# irkit_v02.net
KiCad netlist of a schematic drawn in EAGLE
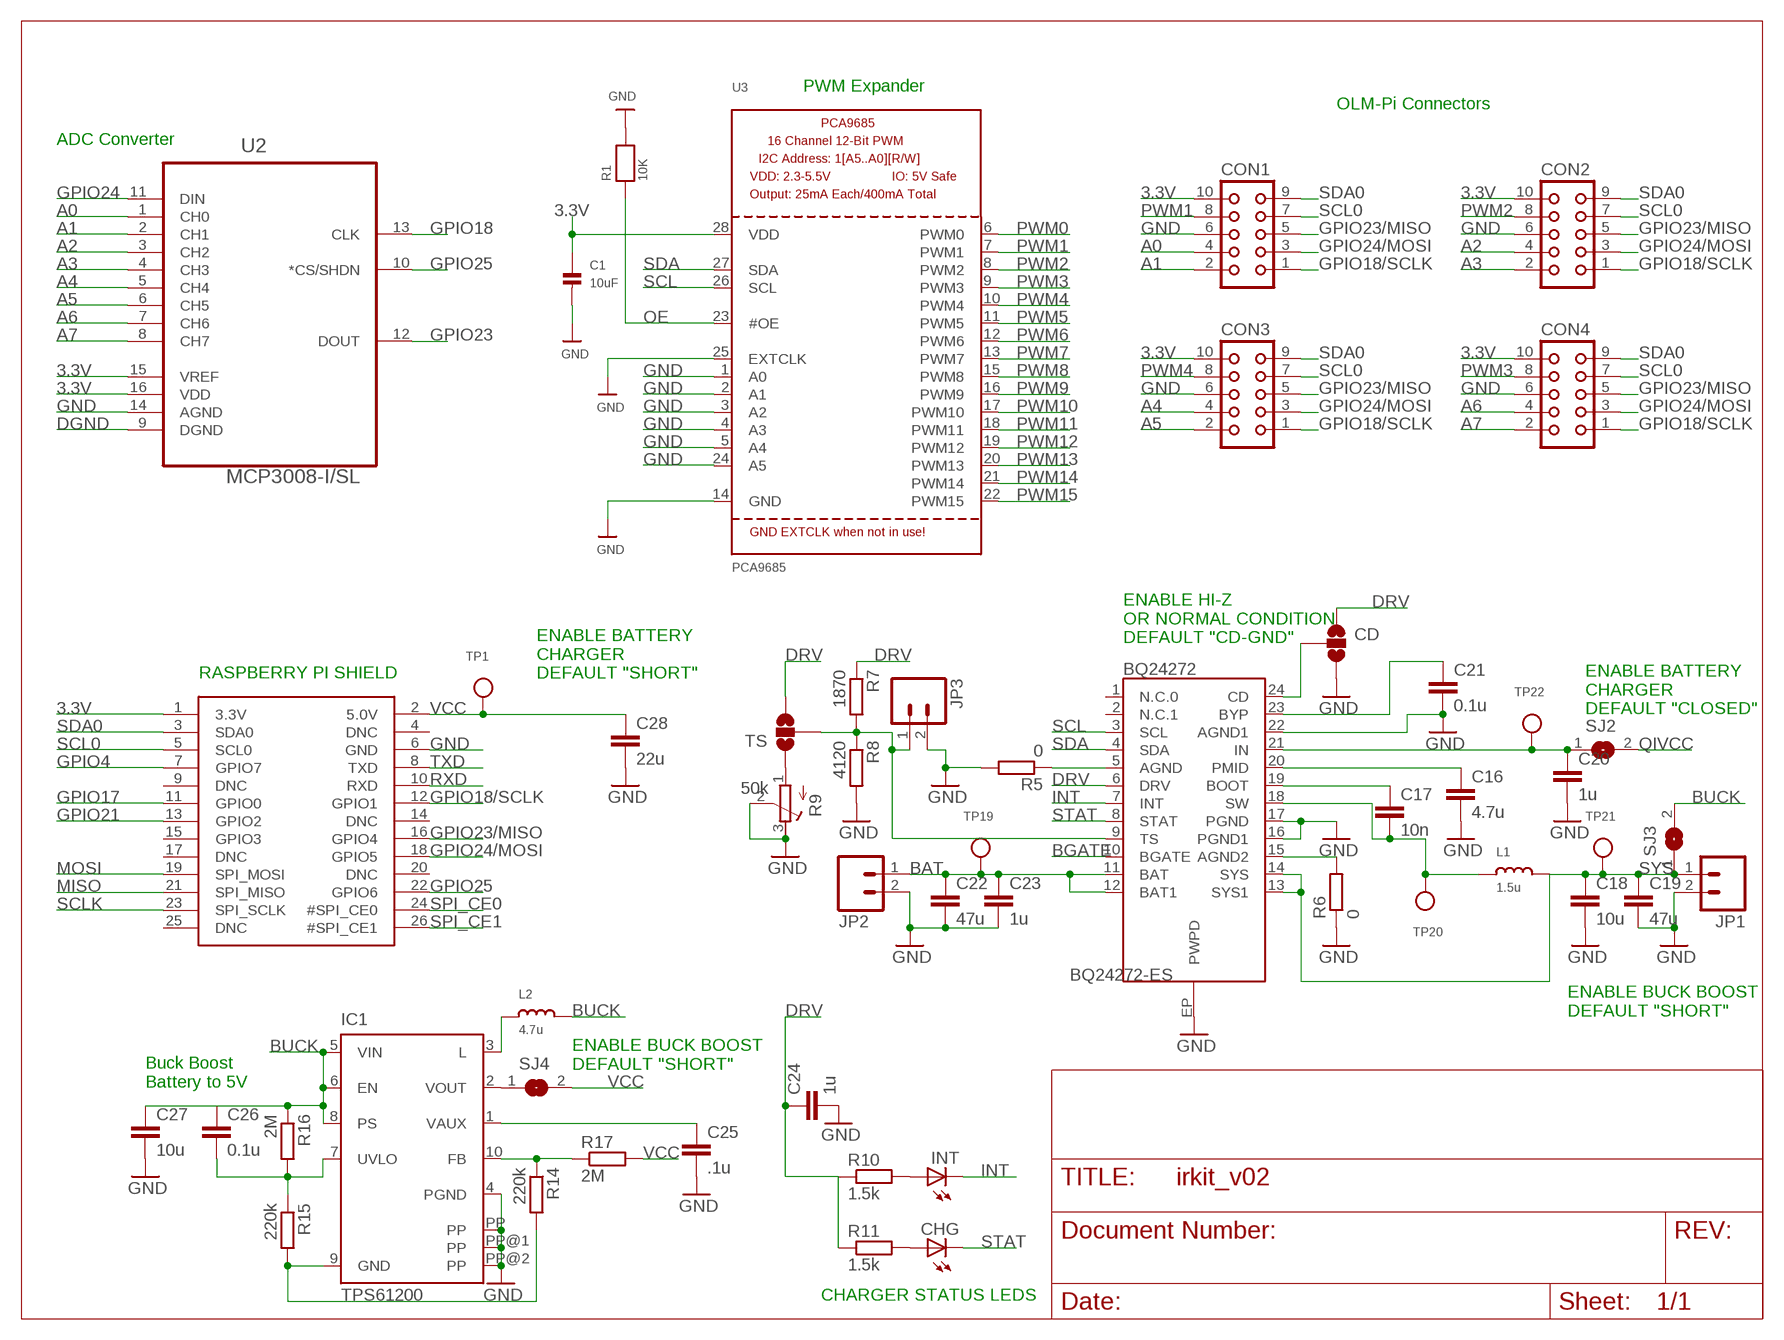
[diagram p0: schematic, sheet 1]

(export (version "E")
  (design (tool "Eeschema 10.0.6"))
  (components
    (comp (ref "BQ24272")
      (value "BQ24272-ES")
      (footprint "eagle-import:QFN-24_ALT2")
      (libsource (lib "eagle-import") (part "BQ24272-ES"))
    )
    (comp (ref "C1")
      (value "10uF")
      (footprint "eagle-import:0805")
      (libsource (lib "eagle-import") (part "CAP_CERAMIC0805"))
    )
    (comp (ref "C16")
      (value "4.7u")
      (footprint "eagle-import:C0603K")
      (libsource (lib "eagle-import") (part "C-EUC0603K"))
    )
    (comp (ref "C17")
      (value "10n")
      (footprint "eagle-import:C0603K")
      (libsource (lib "eagle-import") (part "C-EUC0603K"))
    )
    (comp (ref "C18")
      (value "10u")
      (footprint "eagle-import:C0603K")
      (libsource (lib "eagle-import") (part "C-EUC0603K"))
    )
    (comp (ref "C19")
      (value "47u")
      (footprint "eagle-import:C0603K")
      (libsource (lib "eagle-import") (part "C-EUC0603K"))
    )
    (comp (ref "C20")
      (value "1u")
      (footprint "eagle-import:C0603K")
      (libsource (lib "eagle-import") (part "C-EUC0603K"))
    )
    (comp (ref "C21")
      (value "0.1u")
      (footprint "eagle-import:C0603K")
      (libsource (lib "eagle-import") (part "C-EUC0603K"))
    )
    (comp (ref "C22")
      (value "47u")
      (footprint "eagle-import:C0603K")
      (libsource (lib "eagle-import") (part "C-EUC0603K"))
    )
    (comp (ref "C23")
      (value "1u")
      (footprint "eagle-import:C0603K")
      (libsource (lib "eagle-import") (part "C-EUC0603K"))
    )
    (comp (ref "C24")
      (value "1u")
      (footprint "eagle-import:C0603K")
      (libsource (lib "eagle-import") (part "C-EUC0603K"))
    )
    (comp (ref "C25")
      (value ".1u")
      (footprint "eagle-import:C0603K")
      (libsource (lib "eagle-import") (part "C-EUC0603K"))
    )
    (comp (ref "C26")
      (value "0.1u")
      (footprint "eagle-import:C0603K")
      (libsource (lib "eagle-import") (part "C-EUC0603K"))
    )
    (comp (ref "C27")
      (value "10u")
      (footprint "eagle-import:C0603K")
      (libsource (lib "eagle-import") (part "C-EUC0603K"))
    )
    (comp (ref "C28")
      (value "22u")
      (footprint "eagle-import:C0603K")
      (libsource (lib "eagle-import") (part "C-EUC0603K"))
    )
    (comp (ref "CD")
      (value "SOLDERJUMPER_2WAYS")
      (footprint "eagle-import:SJ_3")
      (libsource (lib "eagle-import") (part "SOLDERJUMPER_2WAYS"))
    )
    (comp (ref "CHG")
      (value "LEDCHIP-LED0603")
      (footprint "eagle-import:CHIP-LED0603")
      (libsource (lib "eagle-import") (part "LEDCHIP-LED0603"))
    )
    (comp (ref "CON1")
      (value "CON10L")
      (footprint "eagle-import:CON10L")
      (libsource (lib "eagle-import") (part "CON10L"))
    )
    (comp (ref "CON2")
      (value "CON10L")
      (footprint "eagle-import:CON10L")
      (libsource (lib "eagle-import") (part "CON10L"))
    )
    (comp (ref "CON3")
      (value "CON10L")
      (footprint "eagle-import:CON10L")
      (libsource (lib "eagle-import") (part "CON10L"))
    )
    (comp (ref "CON4")
      (value "CON10L")
      (footprint "eagle-import:CON10L")
      (libsource (lib "eagle-import") (part "CON10L"))
    )
    (comp (ref "IC1")
      (value "TPS61200")
      (footprint "eagle-import:S-PDSO-N10")
      (fields (field (name "MPN") "TPS61200DRCT"))
      (libsource (lib "eagle-import") (part "TPS61200"))
    )
    (comp (ref "INT")
      (value "LEDCHIP-LED0603")
      (footprint "eagle-import:CHIP-LED0603")
      (libsource (lib "eagle-import") (part "LEDCHIP-LED0603"))
    )
    (comp (ref "JP1")
      (value "M02PTH3")
      (footprint "eagle-import:1X02_LONGPADS")
      (libsource (lib "eagle-import") (part "M02PTH3"))
    )
    (comp (ref "JP2")
      (value "M02PTH3")
      (footprint "eagle-import:1X02_LONGPADS")
      (libsource (lib "eagle-import") (part "M02PTH3"))
    )
    (comp (ref "JP3")
      (value "M02PTH3")
      (footprint "eagle-import:1X02_LONGPADS")
      (libsource (lib "eagle-import") (part "M02PTH3"))
    )
    (comp (ref "L1")
      (value "1.5u")
      (footprint "eagle-import:INDUCTOR_5X5MM_NR5040_NOTHERMALS")
      (libsource (lib "eagle-import") (part "INDUCTORNR5040"))
    )
    (comp (ref "L2")
      (value "4.7u")
      (footprint "eagle-import:INDUCTOR_5X5MM_NR5040_NOTHERMALS")
      (libsource (lib "eagle-import") (part "INDUCTORNR5040"))
    )
    (comp (ref "R1")
      (value "10K")
      (footprint "eagle-import:0805")
      (libsource (lib "eagle-import") (part "RESISTOR0805"))
    )
    (comp (ref "R5")
      (value "0")
      (footprint "eagle-import:R0402")
      (fields (field (name "MPN") "ERJ3EKF3000V"))
      (libsource (lib "eagle-import") (part "R-EU_R0402"))
    )
    (comp (ref "R6")
      (value "0")
      (footprint "eagle-import:R0402")
      (fields (field (name "MPN") "ERJ3EKF3000V"))
      (libsource (lib "eagle-import") (part "R-EU_R0402"))
    )
    (comp (ref "R7")
      (value "1870")
      (footprint "eagle-import:R0402")
      (fields (field (name "MPN") "ERJ3EKF3000V"))
      (libsource (lib "eagle-import") (part "R-EU_R0402"))
    )
    (comp (ref "R8")
      (value "4120")
      (footprint "eagle-import:R0402")
      (fields (field (name "MPN") "ERJ3EKF3000V"))
      (libsource (lib "eagle-import") (part "R-EU_R0402"))
    )
    (comp (ref "R9")
      (value "50k")
      (footprint "eagle-import:RTRIM64Y")
      (libsource (lib "eagle-import") (part "R-TRIMM64Y"))
    )
    (comp (ref "R10")
      (value "1.5k")
      (footprint "eagle-import:R0402")
      (fields (field (name "MPN") "ERJ3EKF3000V"))
      (libsource (lib "eagle-import") (part "R-EU_R0402"))
    )
    (comp (ref "R11")
      (value "1.5k")
      (footprint "eagle-import:R0402")
      (fields (field (name "MPN") "ERJ3EKF3000V"))
      (libsource (lib "eagle-import") (part "R-EU_R0402"))
    )
    (comp (ref "R14")
      (value "220k")
      (footprint "eagle-import:R0402")
      (fields (field (name "MPN") "ERJ3EKF3000V"))
      (libsource (lib "eagle-import") (part "R-EU_R0402"))
    )
    (comp (ref "R15")
      (value "220k")
      (footprint "eagle-import:R0402")
      (fields (field (name "MPN") "ERJ3EKF3000V"))
      (libsource (lib "eagle-import") (part "R-EU_R0402"))
    )
    (comp (ref "R16")
      (value "2M")
      (footprint "eagle-import:R0402")
      (fields (field (name "MPN") "ERJ3EKF3000V"))
      (libsource (lib "eagle-import") (part "R-EU_R0402"))
    )
    (comp (ref "R17")
      (value "2M")
      (footprint "eagle-import:R0402")
      (fields (field (name "MPN") "ERJ3EKF3000V"))
      (libsource (lib "eagle-import") (part "R-EU_R0402"))
    )
    (comp (ref "SJ2") (value "SJ") (footprint "eagle-import:SJ") (libsource (lib "eagle-import") (part "SJ")))
    (comp (ref "SJ3") (value "SJ") (footprint "eagle-import:SJ") (libsource (lib "eagle-import") (part "SJ")))
    (comp (ref "SJ4") (value "SJ") (footprint "eagle-import:SJ") (libsource (lib "eagle-import") (part "SJ")))
    (comp (ref "TP1")
      (value "TESTPOINTROUND1MM")
      (footprint "eagle-import:TESTPOINT_ROUND_1MM")
      (libsource (lib "eagle-import") (part "TESTPOINTROUND1MM"))
    )
    (comp (ref "TP19")
      (value "TESTPOINTROUND1MM")
      (footprint "eagle-import:TESTPOINT_ROUND_1MM")
      (libsource (lib "eagle-import") (part "TESTPOINTROUND1MM"))
    )
    (comp (ref "TP20")
      (value "TESTPOINTROUND1MM")
      (footprint "eagle-import:TESTPOINT_ROUND_1MM")
      (libsource (lib "eagle-import") (part "TESTPOINTROUND1MM"))
    )
    (comp (ref "TP21")
      (value "TESTPOINTROUND1MM")
      (footprint "eagle-import:TESTPOINT_ROUND_1MM")
      (libsource (lib "eagle-import") (part "TESTPOINTROUND1MM"))
    )
    (comp (ref "TP22")
      (value "TESTPOINTROUND1MM")
      (footprint "eagle-import:TESTPOINT_ROUND_1MM")
      (libsource (lib "eagle-import") (part "TESTPOINTROUND1MM"))
    )
    (comp (ref "TS")
      (value "SOLDERJUMPER_2WAYS")
      (footprint "eagle-import:SJ_3")
      (libsource (lib "eagle-import") (part "SOLDERJUMPER_2WAYS"))
    )
    (comp (ref "U$1")
      (value "RASPBERRYPI_BB")
      (footprint "eagle-import:RASBERRYPI_SHIELD")
      (libsource (lib "eagle-import") (part "RASPBERRYPI_BB"))
    )
    (comp (ref "U2")
      (value "MCP3008-I/SL")
      (footprint "eagle-import:SOIC127P600X175-16N")
      (libsource (lib "eagle-import") (part "MCP3008-I/SL"))
    )
    (comp (ref "U3")
      (value "PCA9685")
      (footprint "eagle-import:TSSOP28")
      (libsource (lib "eagle-import") (part "PCA9685"))
    )
  )
  (nets
    (net (code "1") (name "/3.3V") (class "Default")
      (node (ref "C1") (pin "1") (pinfunction "P$1_1") (pintype "passive"))
      (node (ref "CON1") (pin "10") (pinfunction "10_10") (pintype "passive"))
      (node (ref "CON2") (pin "10") (pinfunction "10_10") (pintype "passive"))
      (node (ref "CON3") (pin "10") (pinfunction "10_10") (pintype "passive"))
      (node (ref "CON4") (pin "10") (pinfunction "10_10") (pintype "passive"))
      (node (ref "U$1") (pin "1") (pinfunction "3.3V_1") (pintype "power_in"))
      (node (ref "U2") (pin "15") (pinfunction "VREF_15") (pintype "input"))
      (node (ref "U2") (pin "16") (pinfunction "VDD_16") (pintype "power_in"))
      (node (ref "U3") (pin "28") (pinfunction "VDD_28") (pintype "power_in"))
    )
    (net (code "2") (name "/A0") (class "Default")
      (node (ref "CON1") (pin "4") (pinfunction "4_4") (pintype "passive"))
      (node (ref "U2") (pin "1") (pinfunction "CH0_1") (pintype "input"))
    )
    (net (code "3") (name "/A1") (class "Default")
      (node (ref "CON1") (pin "2") (pinfunction "2_2") (pintype "passive"))
      (node (ref "U2") (pin "2") (pinfunction "CH1_2") (pintype "input"))
    )
    (net (code "4") (name "/A2") (class "Default")
      (node (ref "CON2") (pin "4") (pinfunction "4_4") (pintype "passive"))
      (node (ref "U2") (pin "3") (pinfunction "CH2_3") (pintype "input"))
    )
    (net (code "5") (name "/A3") (class "Default")
      (node (ref "CON2") (pin "2") (pinfunction "2_2") (pintype "passive"))
      (node (ref "U2") (pin "4") (pinfunction "CH3_4") (pintype "input"))
    )
    (net (code "6") (name "/A4") (class "Default")
      (node (ref "CON3") (pin "4") (pinfunction "4_4") (pintype "passive"))
      (node (ref "U2") (pin "5") (pinfunction "CH4_5") (pintype "input"))
    )
    (net (code "7") (name "/A5") (class "Default")
      (node (ref "CON3") (pin "2") (pinfunction "2_2") (pintype "passive"))
      (node (ref "U2") (pin "6") (pinfunction "CH5_6") (pintype "input"))
    )
    (net (code "8") (name "/A6") (class "Default")
      (node (ref "CON4") (pin "4") (pinfunction "4_4") (pintype "passive"))
      (node (ref "U2") (pin "7") (pinfunction "CH6_7") (pintype "input"))
    )
    (net (code "9") (name "/A7") (class "Default")
      (node (ref "CON4") (pin "2") (pinfunction "2_2") (pintype "passive"))
      (node (ref "U2") (pin "8") (pinfunction "CH7_8") (pintype "input"))
    )
    (net (code "10") (name "/BAT") (class "Default")
      (node (ref "BQ24272") (pin "11") (pinfunction "BAT_11") (pintype "bidirectional"))
      (node (ref "BQ24272") (pin "12") (pinfunction "BAT1_12") (pintype "bidirectional"))
      (node (ref "C22") (pin "1") (pinfunction "1_1") (pintype "passive"))
      (node (ref "C23") (pin "1") (pinfunction "1_1") (pintype "passive"))
      (node (ref "JP2") (pin "1") (pinfunction "1_1") (pintype "passive"))
      (node (ref "TP19") (pin "P$1") (pinfunction "P$1_P$1") (pintype "bidirectional"))
    )
    (net (code "11") (name "/BGATE") (class "Default")
      (node (ref "BQ24272") (pin "10") (pinfunction "BGATE_10") (pintype "bidirectional"))
    )
    (net (code "12") (name "/BUCK") (class "Default")
      (node (ref "C26") (pin "1") (pinfunction "1_1") (pintype "passive"))
      (node (ref "C27") (pin "1") (pinfunction "1_1") (pintype "passive"))
      (node (ref "IC1") (pin "5") (pinfunction "VIN_5") (pintype "input"))
      (node (ref "IC1") (pin "6") (pinfunction "EN_6") (pintype "input"))
      (node (ref "IC1") (pin "8") (pinfunction "PS_8") (pintype "input"))
      (node (ref "L2") (pin "P$2") (pinfunction "2_P$2") (pintype "passive"))
      (node (ref "R16") (pin "1") (pinfunction "1_1") (pintype "passive"))
      (node (ref "SJ3") (pin "2") (pinfunction "2_2") (pintype "passive"))
    )
    (net (code "13") (name "/DGND") (class "Default")
      (node (ref "U2") (pin "9") (pinfunction "DGND_9") (pintype "passive"))
    )
    (net (code "14") (name "/DRV") (class "Default")
      (node (ref "BQ24272") (pin "6") (pinfunction "DRV_6") (pintype "bidirectional"))
      (node (ref "C24") (pin "1") (pinfunction "1_1") (pintype "passive"))
      (node (ref "CD") (pin "1") (pinfunction "1_1") (pintype "passive"))
      (node (ref "R10") (pin "1") (pinfunction "1_1") (pintype "passive"))
      (node (ref "R11") (pin "1") (pinfunction "1_1") (pintype "passive"))
      (node (ref "R7") (pin "1") (pinfunction "1_1") (pintype "passive"))
      (node (ref "TS") (pin "3") (pinfunction "3_3") (pintype "passive"))
    )
    (net (code "15") (name "/GPIO4") (class "Default")
      (node (ref "U$1") (pin "7") (pinfunction "GPIO7_7") (pintype "bidirectional"))
    )
    (net (code "16") (name "/GPIO17") (class "Default")
      (node (ref "U$1") (pin "11") (pinfunction "GPIO0_11") (pintype "bidirectional"))
    )
    (net (code "17") (name "/GPIO18") (class "Default")
      (node (ref "U2") (pin "13") (pinfunction "CLK_13") (pintype "input"))
    )
    (net (code "18") (name "/GPIO18{slash}SCLK") (class "Default")
      (node (ref "CON1") (pin "1") (pinfunction "1_1") (pintype "passive"))
      (node (ref "CON2") (pin "1") (pinfunction "1_1") (pintype "passive"))
      (node (ref "CON3") (pin "1") (pinfunction "1_1") (pintype "passive"))
      (node (ref "CON4") (pin "1") (pinfunction "1_1") (pintype "passive"))
      (node (ref "U$1") (pin "12") (pinfunction "GPIO1_12") (pintype "bidirectional"))
    )
    (net (code "19") (name "/GPIO21") (class "Default")
      (node (ref "U$1") (pin "13") (pinfunction "GPIO2_13") (pintype "bidirectional"))
    )
    (net (code "20") (name "/GPIO23") (class "Default")
      (node (ref "U2") (pin "12") (pinfunction "DOUT_12") (pintype "output"))
    )
    (net (code "21") (name "/GPIO23{slash}MISO") (class "Default")
      (node (ref "CON1") (pin "5") (pinfunction "5_5") (pintype "passive"))
      (node (ref "CON2") (pin "5") (pinfunction "5_5") (pintype "passive"))
      (node (ref "CON3") (pin "5") (pinfunction "5_5") (pintype "passive"))
      (node (ref "CON4") (pin "5") (pinfunction "5_5") (pintype "passive"))
      (node (ref "U$1") (pin "16") (pinfunction "GPIO4_16") (pintype "bidirectional"))
    )
    (net (code "22") (name "/GPIO24") (class "Default")
      (node (ref "U2") (pin "11") (pinfunction "DIN_11") (pintype "input"))
    )
    (net (code "23") (name "/GPIO24{slash}MOSI") (class "Default")
      (node (ref "CON1") (pin "3") (pinfunction "3_3") (pintype "passive"))
      (node (ref "CON2") (pin "3") (pinfunction "3_3") (pintype "passive"))
      (node (ref "CON3") (pin "3") (pinfunction "3_3") (pintype "passive"))
      (node (ref "CON4") (pin "3") (pinfunction "3_3") (pintype "passive"))
      (node (ref "U$1") (pin "18") (pinfunction "GPIO5_18") (pintype "bidirectional"))
    )
    (net (code "24") (name "/GPIO25") (class "Default")
      (node (ref "U$1") (pin "22") (pinfunction "GPIO6_22") (pintype "bidirectional"))
      (node (ref "U2") (pin "10") (pinfunction "*CS/SHDN_10") (pintype "input"))
    )
    (net (code "25") (name "/INT") (class "Default")
      (node (ref "BQ24272") (pin "7") (pinfunction "INT_7") (pintype "bidirectional"))
      (node (ref "INT") (pin "C") (pinfunction "C_C") (pintype "passive"))
    )
    (net (code "26") (name "/MISO") (class "Default")
      (node (ref "U$1") (pin "21") (pinfunction "SPI_MISO_21") (pintype "input"))
    )
    (net (code "27") (name "/MOSI") (class "Default")
      (node (ref "U$1") (pin "19") (pinfunction "SPI_MOSI_19") (pintype "output"))
    )
    (net (code "28") (name "/OE") (class "Default")
      (node (ref "R1") (pin "1") (pinfunction "1_1") (pintype "passive"))
      (node (ref "U3") (pin "23") (pinfunction "#OE_23") (pintype "input"))
    )
    (net (code "29") (name "/PWM0") (class "Default")
      (node (ref "U3") (pin "6") (pinfunction "PWM0_6") (pintype "output"))
    )
    (net (code "30") (name "/PWM1") (class "Default")
      (node (ref "CON1") (pin "8") (pinfunction "8_8") (pintype "passive"))
      (node (ref "U3") (pin "7") (pinfunction "PWM1_7") (pintype "output"))
    )
    (net (code "31") (name "/PWM2") (class "Default")
      (node (ref "CON2") (pin "8") (pinfunction "8_8") (pintype "passive"))
      (node (ref "U3") (pin "8") (pinfunction "PWM2_8") (pintype "output"))
    )
    (net (code "32") (name "/PWM3") (class "Default")
      (node (ref "CON4") (pin "8") (pinfunction "8_8") (pintype "passive"))
      (node (ref "U3") (pin "9") (pinfunction "PWM3_9") (pintype "output"))
    )
    (net (code "33") (name "/PWM4") (class "Default")
      (node (ref "CON3") (pin "8") (pinfunction "8_8") (pintype "passive"))
      (node (ref "U3") (pin "10") (pinfunction "PWM4_10") (pintype "output"))
    )
    (net (code "34") (name "/PWM5") (class "Default")
      (node (ref "U3") (pin "11") (pinfunction "PWM5_11") (pintype "output"))
    )
    (net (code "35") (name "/PWM6") (class "Default")
      (node (ref "U3") (pin "12") (pinfunction "PWM6_12") (pintype "output"))
    )
    (net (code "36") (name "/PWM7") (class "Default")
      (node (ref "U3") (pin "13") (pinfunction "PWM7_13") (pintype "output"))
    )
    (net (code "37") (name "/PWM8") (class "Default")
      (node (ref "U3") (pin "15") (pinfunction "PWM8_15") (pintype "output"))
    )
    (net (code "38") (name "/PWM9") (class "Default")
      (node (ref "U3") (pin "16") (pinfunction "PWM9_16") (pintype "output"))
    )
    (net (code "39") (name "/PWM10") (class "Default")
      (node (ref "U3") (pin "17") (pinfunction "PWM10_17") (pintype "output"))
    )
    (net (code "40") (name "/PWM11") (class "Default")
      (node (ref "U3") (pin "18") (pinfunction "PWM11_18") (pintype "output"))
    )
    (net (code "41") (name "/PWM12") (class "Default")
      (node (ref "U3") (pin "19") (pinfunction "PWM12_19") (pintype "output"))
    )
    (net (code "42") (name "/PWM13") (class "Default")
      (node (ref "U3") (pin "20") (pinfunction "PWM13_20") (pintype "output"))
    )
    (net (code "43") (name "/PWM14") (class "Default")
      (node (ref "U3") (pin "21") (pinfunction "PWM14_21") (pintype "output"))
    )
    (net (code "44") (name "/PWM15") (class "Default")
      (node (ref "U3") (pin "22") (pinfunction "PWM15_22") (pintype "output"))
    )
    (net (code "45") (name "/QIVCC") (class "Default")
      (node (ref "SJ2") (pin "2") (pinfunction "2_2") (pintype "passive"))
    )
    (net (code "46") (name "/RXD") (class "Default")
      (node (ref "U$1") (pin "10") (pinfunction "RXD_10") (pintype "input"))
    )
    (net (code "47") (name "/SCL") (class "Default")
      (node (ref "BQ24272") (pin "3") (pinfunction "SCL_3") (pintype "bidirectional"))
      (node (ref "U3") (pin "26") (pinfunction "SCL_26") (pintype "bidirectional"))
    )
    (net (code "48") (name "/SCL0") (class "Default")
      (node (ref "CON1") (pin "7") (pinfunction "7_7") (pintype "passive"))
      (node (ref "CON2") (pin "7") (pinfunction "7_7") (pintype "passive"))
      (node (ref "CON3") (pin "7") (pinfunction "7_7") (pintype "passive"))
      (node (ref "CON4") (pin "7") (pinfunction "7_7") (pintype "passive"))
      (node (ref "U$1") (pin "5") (pinfunction "SCL0_5") (pintype "output"))
    )
    (net (code "49") (name "/SCLK") (class "Default")
      (node (ref "U$1") (pin "23") (pinfunction "SPI_SCLK_23") (pintype "output"))
    )
    (net (code "50") (name "/SDA") (class "Default")
      (node (ref "BQ24272") (pin "4") (pinfunction "SDA_4") (pintype "bidirectional"))
      (node (ref "U3") (pin "27") (pinfunction "SDA_27") (pintype "bidirectional"))
    )
    (net (code "51") (name "/SDA0") (class "Default")
      (node (ref "CON1") (pin "9") (pinfunction "9_9") (pintype "passive"))
      (node (ref "CON2") (pin "9") (pinfunction "9_9") (pintype "passive"))
      (node (ref "CON3") (pin "9") (pinfunction "9_9") (pintype "passive"))
      (node (ref "CON4") (pin "9") (pinfunction "9_9") (pintype "passive"))
      (node (ref "U$1") (pin "3") (pinfunction "SDA0_3") (pintype "bidirectional"))
    )
    (net (code "52") (name "/SPI_CE0") (class "Default")
      (node (ref "U$1") (pin "24") (pinfunction "#SPI_CE0_24") (pintype "output"))
    )
    (net (code "53") (name "/SPI_CE1") (class "Default")
      (node (ref "U$1") (pin "26") (pinfunction "#SPI_CE1_26") (pintype "output"))
    )
    (net (code "54") (name "/STAT") (class "Default")
      (node (ref "BQ24272") (pin "8") (pinfunction "STAT_8") (pintype "bidirectional"))
      (node (ref "CHG") (pin "C") (pinfunction "C_C") (pintype "passive"))
    )
    (net (code "55") (name "/SYS") (class "Default")
      (node (ref "BQ24272") (pin "13") (pinfunction "SYS1_13") (pintype "bidirectional"))
      (node (ref "BQ24272") (pin "14") (pinfunction "SYS_14") (pintype "bidirectional"))
      (node (ref "C18") (pin "1") (pinfunction "1_1") (pintype "passive"))
      (node (ref "C19") (pin "1") (pinfunction "1_1") (pintype "passive"))
      (node (ref "JP1") (pin "1") (pinfunction "1_1") (pintype "passive"))
      (node (ref "L1") (pin "P$2") (pinfunction "2_P$2") (pintype "passive"))
      (node (ref "SJ3") (pin "1") (pinfunction "1_1") (pintype "passive"))
      (node (ref "TP21") (pin "P$1") (pinfunction "P$1_P$1") (pintype "bidirectional"))
    )
    (net (code "56") (name "/TXD") (class "Default")
      (node (ref "U$1") (pin "8") (pinfunction "TXD_8") (pintype "output"))
    )
    (net (code "57") (name "/VCC") (class "Default")
      (node (ref "C28") (pin "1") (pinfunction "1_1") (pintype "passive"))
      (node (ref "R17") (pin "2") (pinfunction "2_2") (pintype "passive"))
      (node (ref "SJ4") (pin "2") (pinfunction "2_2") (pintype "passive"))
      (node (ref "TP1") (pin "P$1") (pinfunction "P$1_P$1") (pintype "bidirectional"))
      (node (ref "U$1") (pin "2") (pinfunction "5.0V_2") (pintype "power_in"))
    )
    (net (code "58") (name "GND") (class "Default")
      (node (ref "BQ24272") (pin "16") (pinfunction "PGND1_16") (pintype "bidirectional"))
      (node (ref "BQ24272") (pin "17") (pinfunction "PGND_17") (pintype "bidirectional"))
      (node (ref "BQ24272") (pin "22") (pinfunction "AGND1_22") (pintype "bidirectional"))
      (node (ref "BQ24272") (pin "EP") (pinfunction "PWPD_EP") (pintype "bidirectional"))
      (node (ref "C1") (pin "2") (pinfunction "P$2_2") (pintype "passive"))
      (node (ref "C16") (pin "2") (pinfunction "2_2") (pintype "passive"))
      (node (ref "C18") (pin "2") (pinfunction "2_2") (pintype "passive"))
      (node (ref "C19") (pin "2") (pinfunction "2_2") (pintype "passive"))
      (node (ref "C20") (pin "2") (pinfunction "2_2") (pintype "passive"))
      (node (ref "C21") (pin "2") (pinfunction "2_2") (pintype "passive"))
      (node (ref "C22") (pin "2") (pinfunction "2_2") (pintype "passive"))
      (node (ref "C23") (pin "2") (pinfunction "2_2") (pintype "passive"))
      (node (ref "C24") (pin "2") (pinfunction "2_2") (pintype "passive"))
      (node (ref "C25") (pin "2") (pinfunction "2_2") (pintype "passive"))
      (node (ref "C27") (pin "2") (pinfunction "2_2") (pintype "passive"))
      (node (ref "C28") (pin "2") (pinfunction "2_2") (pintype "passive"))
      (node (ref "CD") (pin "3") (pinfunction "3_3") (pintype "passive"))
      (node (ref "CON1") (pin "6") (pinfunction "6_6") (pintype "passive"))
      (node (ref "CON2") (pin "6") (pinfunction "6_6") (pintype "passive"))
      (node (ref "CON3") (pin "6") (pinfunction "6_6") (pintype "passive"))
      (node (ref "CON4") (pin "6") (pinfunction "6_6") (pintype "passive"))
      (node (ref "IC1") (pin "4") (pinfunction "PGND_4") (pintype "power_in"))
      (node (ref "IC1") (pin "PP") (pinfunction "PP_PP") (pintype "power_in"))
      (node (ref "IC1") (pin "PP@1") (pinfunction "PP_PP@1") (pintype "power_in"))
      (node (ref "IC1") (pin "PP@2") (pinfunction "PP_PP@2") (pintype "power_in"))
      (node (ref "JP1") (pin "2") (pinfunction "2_2") (pintype "passive"))
      (node (ref "JP2") (pin "2") (pinfunction "2_2") (pintype "passive"))
      (node (ref "JP3") (pin "2") (pinfunction "2_2") (pintype "passive"))
      (node (ref "R1") (pin "2") (pinfunction "2_2") (pintype "passive"))
      (node (ref "R5") (pin "2") (pinfunction "2_2") (pintype "passive"))
      (node (ref "R6") (pin "1") (pinfunction "1_1") (pintype "passive"))
      (node (ref "R8") (pin "2") (pinfunction "2_2") (pintype "passive"))
      (node (ref "R9") (pin "2") (pinfunction "S_2") (pintype "passive"))
      (node (ref "R9") (pin "3") (pinfunction "E_3") (pintype "passive"))
      (node (ref "U$1") (pin "6") (pinfunction "GND_6") (pintype "power_in"))
      (node (ref "U2") (pin "14") (pinfunction "AGND_14") (pintype "passive"))
      (node (ref "U3") (pin "1") (pinfunction "A0_1") (pintype "bidirectional"))
      (node (ref "U3") (pin "14") (pinfunction "GND_14") (pintype "power_in"))
      (node (ref "U3") (pin "2") (pinfunction "A1_2") (pintype "bidirectional"))
      (node (ref "U3") (pin "24") (pinfunction "A5_24") (pintype "bidirectional"))
      (node (ref "U3") (pin "25") (pinfunction "EXTCLK_25") (pintype "input"))
      (node (ref "U3") (pin "3") (pinfunction "A2_3") (pintype "bidirectional"))
      (node (ref "U3") (pin "4") (pinfunction "A3_4") (pintype "bidirectional"))
      (node (ref "U3") (pin "5") (pinfunction "A4_5") (pintype "bidirectional"))
    )
    (net (code "59") (name "Net-(BQ24272-AGND)") (class "Default")
      (node (ref "BQ24272") (pin "5") (pinfunction "AGND_5") (pintype "bidirectional"))
      (node (ref "R5") (pin "1") (pinfunction "1_1") (pintype "passive"))
    )
    (net (code "60") (name "Net-(BQ24272-AGND2)") (class "Default")
      (node (ref "BQ24272") (pin "15") (pinfunction "AGND2_15") (pintype "bidirectional"))
      (node (ref "R6") (pin "2") (pinfunction "2_2") (pintype "passive"))
    )
    (net (code "61") (name "Net-(BQ24272-BOOT)") (class "Default")
      (node (ref "BQ24272") (pin "19") (pinfunction "BOOT_19") (pintype "bidirectional"))
      (node (ref "C17") (pin "1") (pinfunction "1_1") (pintype "passive"))
    )
    (net (code "62") (name "Net-(BQ24272-BYP)") (class "Default")
      (node (ref "BQ24272") (pin "23") (pinfunction "BYP_23") (pintype "bidirectional"))
      (node (ref "C21") (pin "1") (pinfunction "1_1") (pintype "passive"))
    )
    (net (code "63") (name "Net-(BQ24272-CD)") (class "Default")
      (node (ref "BQ24272") (pin "24") (pinfunction "CD_24") (pintype "bidirectional"))
      (node (ref "CD") (pin "2") (pinfunction "2_2") (pintype "passive"))
    )
    (net (code "64") (name "Net-(BQ24272-IN)") (class "Default")
      (node (ref "BQ24272") (pin "21") (pinfunction "IN_21") (pintype "bidirectional"))
      (node (ref "C20") (pin "1") (pinfunction "1_1") (pintype "passive"))
      (node (ref "SJ2") (pin "1") (pinfunction "1_1") (pintype "passive"))
      (node (ref "TP22") (pin "P$1") (pinfunction "P$1_P$1") (pintype "bidirectional"))
    )
    (net (code "65") (name "Net-(BQ24272-PMID)") (class "Default")
      (node (ref "BQ24272") (pin "20") (pinfunction "PMID_20") (pintype "bidirectional"))
      (node (ref "C16") (pin "1") (pinfunction "1_1") (pintype "passive"))
    )
    (net (code "66") (name "Net-(BQ24272-SW)") (class "Default")
      (node (ref "BQ24272") (pin "18") (pinfunction "SW_18") (pintype "bidirectional"))
      (node (ref "C17") (pin "2") (pinfunction "2_2") (pintype "passive"))
      (node (ref "L1") (pin "P$1") (pinfunction "1_P$1") (pintype "passive"))
      (node (ref "TP20") (pin "P$1") (pinfunction "P$1_P$1") (pintype "bidirectional"))
    )
    (net (code "67") (name "Net-(BQ24272-TS)") (class "Default")
      (node (ref "BQ24272") (pin "9") (pinfunction "TS_9") (pintype "bidirectional"))
      (node (ref "JP3") (pin "1") (pinfunction "1_1") (pintype "passive"))
      (node (ref "R7") (pin "2") (pinfunction "2_2") (pintype "passive"))
      (node (ref "R8") (pin "1") (pinfunction "1_1") (pintype "passive"))
      (node (ref "TS") (pin "2") (pinfunction "2_2") (pintype "passive"))
    )
    (net (code "68") (name "Net-(CHG-PadA)") (class "Default")
      (node (ref "CHG") (pin "A") (pinfunction "A_A") (pintype "passive"))
      (node (ref "R11") (pin "2") (pinfunction "2_2") (pintype "passive"))
    )
    (net (code "69") (name "Net-(IC1-FB)") (class "Default")
      (node (ref "IC1") (pin "10") (pinfunction "FB_10") (pintype "input"))
      (node (ref "R14") (pin "1") (pinfunction "1_1") (pintype "passive"))
      (node (ref "R17") (pin "1") (pinfunction "1_1") (pintype "passive"))
    )
    (net (code "70") (name "Net-(IC1-GND)") (class "Default")
      (node (ref "IC1") (pin "9") (pinfunction "GND_9") (pintype "power_in"))
      (node (ref "R14") (pin "2") (pinfunction "2_2") (pintype "passive"))
      (node (ref "R15") (pin "2") (pinfunction "2_2") (pintype "passive"))
    )
    (net (code "71") (name "Net-(IC1-L)") (class "Default")
      (node (ref "IC1") (pin "3") (pinfunction "L_3") (pintype "input"))
      (node (ref "L2") (pin "P$1") (pinfunction "1_P$1") (pintype "passive"))
    )
    (net (code "72") (name "Net-(IC1-UVLO)") (class "Default")
      (node (ref "C26") (pin "2") (pinfunction "2_2") (pintype "passive"))
      (node (ref "IC1") (pin "7") (pinfunction "UVLO_7") (pintype "input"))
      (node (ref "R15") (pin "1") (pinfunction "1_1") (pintype "passive"))
      (node (ref "R16") (pin "2") (pinfunction "2_2") (pintype "passive"))
    )
    (net (code "73") (name "Net-(IC1-VAUX)") (class "Default")
      (node (ref "C25") (pin "1") (pinfunction "1_1") (pintype "passive"))
      (node (ref "IC1") (pin "1") (pinfunction "VAUX_1") (pintype "bidirectional"))
    )
    (net (code "74") (name "Net-(IC1-VOUT)") (class "Default")
      (node (ref "IC1") (pin "2") (pinfunction "VOUT_2") (pintype "passive"))
      (node (ref "SJ4") (pin "1") (pinfunction "1_1") (pintype "passive"))
    )
    (net (code "75") (name "Net-(INT-PadA)") (class "Default")
      (node (ref "INT") (pin "A") (pinfunction "A_A") (pintype "passive"))
      (node (ref "R10") (pin "2") (pinfunction "2_2") (pintype "passive"))
    )
    (net (code "76") (name "Net-(R9-A)") (class "Default")
      (node (ref "R9") (pin "1") (pinfunction "A_1") (pintype "passive"))
      (node (ref "TS") (pin "1") (pinfunction "1_1") (pintype "passive"))
    )
    (net (code "77") (name "unconnected-(BQ24272-N.C.0-Pad1)") (class "Default")
      (node (ref "BQ24272") (pin "1") (pinfunction "N.C.0_1") (pintype "bidirectional"))
    )
    (net (code "78") (name "unconnected-(BQ24272-N.C.1-Pad2)") (class "Default")
      (node (ref "BQ24272") (pin "2") (pinfunction "N.C.1_2") (pintype "bidirectional"))
    )
    (net (code "79") (name "unconnected-(U$1-DNC-Pad4)") (class "Default")
      (node (ref "U$1") (pin "4") (pinfunction "DNC_4") (pintype "no_connect"))
    )
    (net (code "80") (name "unconnected-(U$1-DNC-Pad9)") (class "Default")
      (node (ref "U$1") (pin "9") (pinfunction "DNC_9") (pintype "no_connect"))
    )
    (net (code "81") (name "unconnected-(U$1-DNC-Pad14)") (class "Default")
      (node (ref "U$1") (pin "14") (pinfunction "DNC_14") (pintype "no_connect"))
    )
    (net (code "82") (name "unconnected-(U$1-DNC-Pad17)") (class "Default")
      (node (ref "U$1") (pin "17") (pinfunction "DNC_17") (pintype "no_connect"))
    )
    (net (code "83") (name "unconnected-(U$1-DNC-Pad20)") (class "Default")
      (node (ref "U$1") (pin "20") (pinfunction "DNC_20") (pintype "no_connect"))
    )
    (net (code "84") (name "unconnected-(U$1-DNC-Pad25)") (class "Default")
      (node (ref "U$1") (pin "25") (pinfunction "DNC_25") (pintype "no_connect"))
    )
    (net (code "85") (name "unconnected-(U$1-GPIO3-Pad15)") (class "Default")
      (node (ref "U$1") (pin "15") (pinfunction "GPIO3_15") (pintype "bidirectional"))
    )
  )
)
